# Connector.net
KiCad netlist of a schematic drawn in Altium Designer
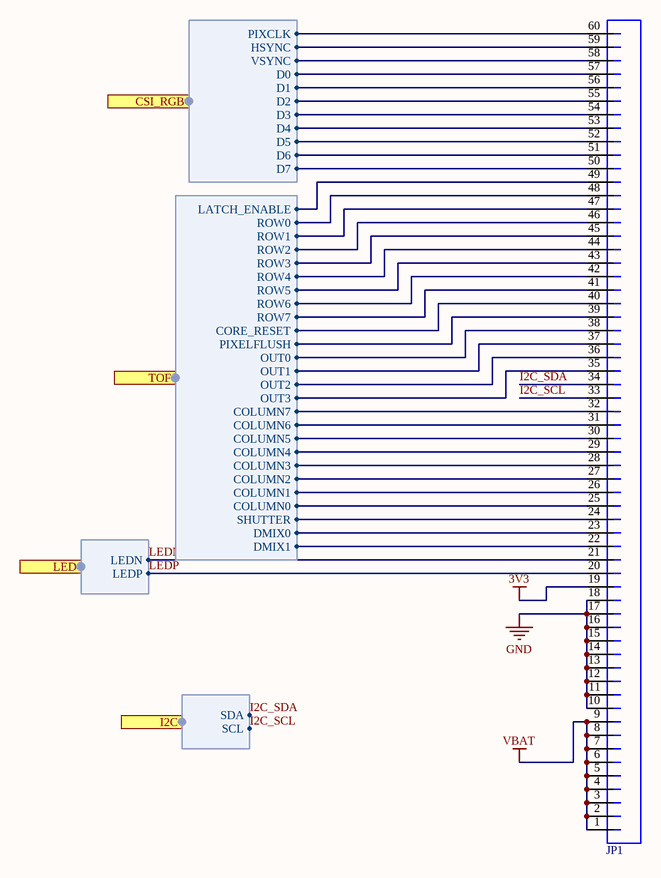
[diagram p0: Connector.SchDoc]

(export (version "E")
  (design (tool "Eeschema 10.0.6"))
  (components
    (comp (ref "JP1")
      (value "JST_JMD_60_RECEPTACLE")
      (footprint "JST-JMD-60-SMD-RECEPTACLE")
      (fields
        (field (name "MANUFACTURER") "JST Sales America, Inc.")
        (field (name "PARTNUMBER") "60R-JMDSS-G-1-TF(S)")
      )
      (libsource (lib "Connectors") (part "JST_JMD_60_RECEPTACLE"))
    )
  )
  (nets
    (net (code "5") (name "/COLUMN0") (class "Default")
      (node (ref "JP1") (pin "25") (pinfunction "25_25") (pintype "passive"))
    )
    (net (code "6") (name "/COLUMN1") (class "Default")
      (node (ref "JP1") (pin "26") (pinfunction "26_26") (pintype "passive"))
    )
    (net (code "7") (name "/COLUMN2") (class "Default")
      (node (ref "JP1") (pin "27") (pinfunction "27_27") (pintype "passive"))
    )
    (net (code "8") (name "/COLUMN3") (class "Default")
      (node (ref "JP1") (pin "28") (pinfunction "28_28") (pintype "passive"))
    )
    (net (code "9") (name "/COLUMN4") (class "Default")
      (node (ref "JP1") (pin "29") (pinfunction "29_29") (pintype "passive"))
    )
    (net (code "10") (name "/COLUMN5") (class "Default")
      (node (ref "JP1") (pin "30") (pinfunction "30_30") (pintype "passive"))
    )
    (net (code "11") (name "/COLUMN6") (class "Default")
      (node (ref "JP1") (pin "31") (pinfunction "31_31") (pintype "passive"))
    )
    (net (code "12") (name "/COLUMN7") (class "Default")
      (node (ref "JP1") (pin "32") (pinfunction "32_32") (pintype "passive"))
    )
    (net (code "13") (name "/CORE_RESET") (class "Default")
      (node (ref "JP1") (pin "40") (pinfunction "40_40") (pintype "passive"))
    )
    (net (code "14") (name "/D0") (class "Default")
      (node (ref "JP1") (pin "57") (pinfunction "57_57") (pintype "passive"))
    )
    (net (code "15") (name "/D1") (class "Default")
      (node (ref "JP1") (pin "56") (pinfunction "56_56") (pintype "passive"))
    )
    (net (code "16") (name "/D2") (class "Default")
      (node (ref "JP1") (pin "55") (pinfunction "55_55") (pintype "passive"))
    )
    (net (code "17") (name "/D3") (class "Default")
      (node (ref "JP1") (pin "54") (pinfunction "54_54") (pintype "passive"))
    )
    (net (code "18") (name "/D4") (class "Default")
      (node (ref "JP1") (pin "53") (pinfunction "53_53") (pintype "passive"))
    )
    (net (code "19") (name "/D5") (class "Default")
      (node (ref "JP1") (pin "52") (pinfunction "52_52") (pintype "passive"))
    )
    (net (code "20") (name "/D6") (class "Default")
      (node (ref "JP1") (pin "51") (pinfunction "51_51") (pintype "passive"))
    )
    (net (code "21") (name "/D7") (class "Default")
      (node (ref "JP1") (pin "50") (pinfunction "50_50") (pintype "passive"))
    )
    (net (code "22") (name "/DMIX0") (class "Default")
      (node (ref "JP1") (pin "23") (pinfunction "23_23") (pintype "passive"))
    )
    (net (code "23") (name "/DMIX1") (class "Default")
      (node (ref "JP1") (pin "22") (pinfunction "22_22") (pintype "passive"))
    )
    (net (code "24") (name "/HSYNC") (class "Default")
      (node (ref "JP1") (pin "59") (pinfunction "59_59") (pintype "passive"))
    )
    (net (code "25") (name "/I2C_SCL") (class "Default")
      (node (ref "JP1") (pin "33") (pinfunction "33_33") (pintype "passive"))
    )
    (net (code "26") (name "/I2C_SDA") (class "Default")
      (node (ref "JP1") (pin "34") (pinfunction "34_34") (pintype "passive"))
    )
    (net (code "27") (name "/LATCH_ENABLE") (class "Default")
      (node (ref "JP1") (pin "49") (pinfunction "49_49") (pintype "passive"))
    )
    (net (code "28") (name "/LEDN") (class "Default")
      (node (ref "JP1") (pin "21") (pinfunction "21_21") (pintype "passive"))
    )
    (net (code "29") (name "/LEDP") (class "Default")
      (node (ref "JP1") (pin "20") (pinfunction "20_20") (pintype "passive"))
    )
    (net (code "30") (name "/OUT0") (class "Default")
      (node (ref "JP1") (pin "38") (pinfunction "38_38") (pintype "passive"))
    )
    (net (code "31") (name "/OUT1") (class "Default")
      (node (ref "JP1") (pin "37") (pinfunction "37_37") (pintype "passive"))
    )
    (net (code "32") (name "/OUT2") (class "Default")
      (node (ref "JP1") (pin "36") (pinfunction "36_36") (pintype "passive"))
    )
    (net (code "33") (name "/OUT3") (class "Default")
      (node (ref "JP1") (pin "35") (pinfunction "35_35") (pintype "passive"))
    )
    (net (code "34") (name "/PIXCLK") (class "Default")
      (node (ref "JP1") (pin "60") (pinfunction "60_60") (pintype "passive"))
    )
    (net (code "35") (name "/PIXELFLUSH") (class "Default")
      (node (ref "JP1") (pin "39") (pinfunction "39_39") (pintype "passive"))
    )
    (net (code "36") (name "/ROW0") (class "Default")
      (node (ref "JP1") (pin "48") (pinfunction "48_48") (pintype "passive"))
    )
    (net (code "37") (name "/ROW1") (class "Default")
      (node (ref "JP1") (pin "47") (pinfunction "47_47") (pintype "passive"))
    )
    (net (code "38") (name "/ROW2") (class "Default")
      (node (ref "JP1") (pin "46") (pinfunction "46_46") (pintype "passive"))
    )
    (net (code "39") (name "/ROW3") (class "Default")
      (node (ref "JP1") (pin "45") (pinfunction "45_45") (pintype "passive"))
    )
    (net (code "40") (name "/ROW4") (class "Default")
      (node (ref "JP1") (pin "44") (pinfunction "44_44") (pintype "passive"))
    )
    (net (code "41") (name "/ROW5") (class "Default")
      (node (ref "JP1") (pin "43") (pinfunction "43_43") (pintype "passive"))
    )
    (net (code "42") (name "/ROW6") (class "Default")
      (node (ref "JP1") (pin "42") (pinfunction "42_42") (pintype "passive"))
    )
    (net (code "43") (name "/ROW7") (class "Default")
      (node (ref "JP1") (pin "41") (pinfunction "41_41") (pintype "passive"))
    )
    (net (code "44") (name "/SHUTTER") (class "Default")
      (node (ref "JP1") (pin "24") (pinfunction "24_24") (pintype "passive"))
    )
    (net (code "45") (name "/VSYNC") (class "Default")
      (node (ref "JP1") (pin "58") (pinfunction "58_58") (pintype "passive"))
    )
    (net (code "50") (name "3V3") (class "Default")
      (node (ref "JP1") (pin "19") (pinfunction "19_19") (pintype "passive"))
    )
    (net (code "51") (name "GND") (class "Default")
      (node (ref "JP1") (pin "10") (pinfunction "10_10") (pintype "passive"))
      (node (ref "JP1") (pin "11") (pinfunction "11_11") (pintype "passive"))
      (node (ref "JP1") (pin "12") (pinfunction "12_12") (pintype "passive"))
      (node (ref "JP1") (pin "13") (pinfunction "13_13") (pintype "passive"))
      (node (ref "JP1") (pin "14") (pinfunction "14_14") (pintype "passive"))
      (node (ref "JP1") (pin "15") (pinfunction "15_15") (pintype "passive"))
      (node (ref "JP1") (pin "16") (pinfunction "16_16") (pintype "passive"))
      (node (ref "JP1") (pin "17") (pinfunction "17_17") (pintype "passive"))
      (node (ref "JP1") (pin "18") (pinfunction "18_18") (pintype "passive"))
    )
    (net (code "52") (name "VBAT") (class "Default")
      (node (ref "JP1") (pin "1") (pinfunction "1_1") (pintype "passive"))
      (node (ref "JP1") (pin "2") (pinfunction "2_2") (pintype "passive"))
      (node (ref "JP1") (pin "3") (pinfunction "3_3") (pintype "passive"))
      (node (ref "JP1") (pin "4") (pinfunction "4_4") (pintype "passive"))
      (node (ref "JP1") (pin "5") (pinfunction "5_5") (pintype "passive"))
      (node (ref "JP1") (pin "6") (pinfunction "6_6") (pintype "passive"))
      (node (ref "JP1") (pin "7") (pinfunction "7_7") (pintype "passive"))
      (node (ref "JP1") (pin "8") (pinfunction "8_8") (pintype "passive"))
      (node (ref "JP1") (pin "9") (pinfunction "9_9") (pintype "passive"))
    )
  )
)
